# Sheet_X_link.net
KiCad netlist of a schematic drawn in Altium Designer
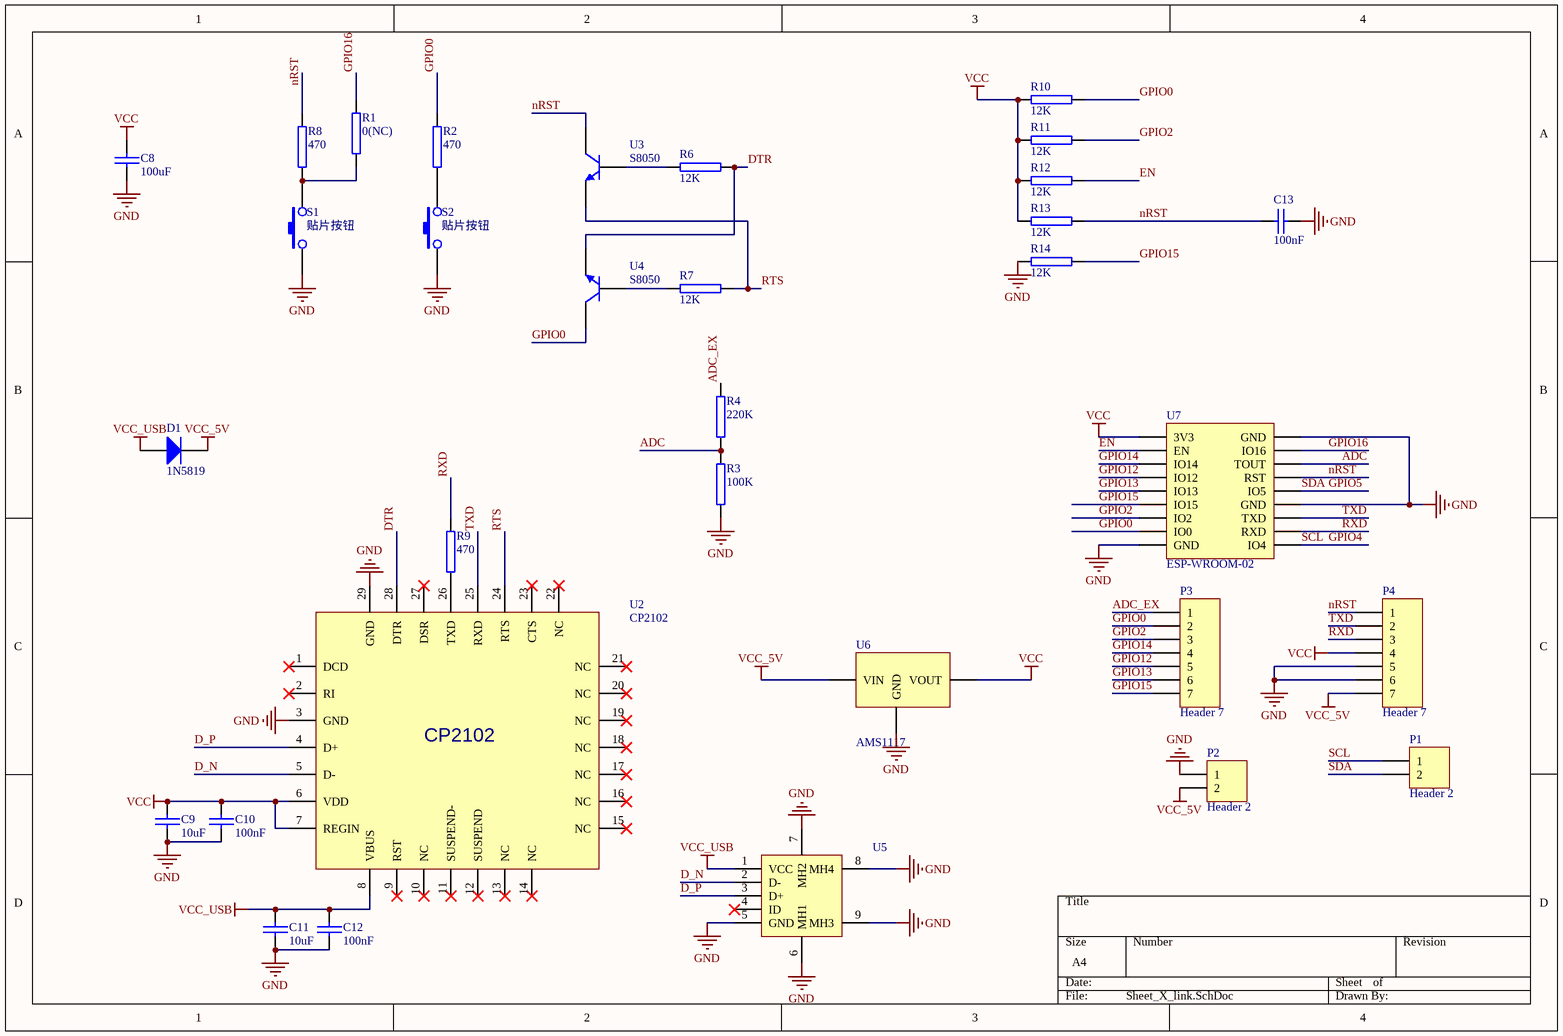
[diagram p0: Sheet_X_link.SchDoc]

(export (version "E")
  (design (tool "Eeschema 10.0.6"))
  (components
    (comp (ref "C8")
      (value "100uF")
      (footprint "C3528")
      (description "贴片电容")
      (libsource (lib "Schlib_OLEDMCU") (part "C0603"))
    )
    (comp (ref "C9")
      (value "10uF")
      (footprint "C0603")
      (description "贴片电容")
      (libsource (lib "Schlib_OLEDMCU") (part "C0603"))
    )
    (comp (ref "C10")
      (value "100nF")
      (footprint "C0603")
      (description "贴片电容")
      (libsource (lib "Schlib_OLEDMCU") (part "C0603"))
    )
    (comp (ref "C11")
      (value "10uF")
      (footprint "C0603")
      (description "贴片电容")
      (libsource (lib "Schlib_OLEDMCU") (part "C0603"))
    )
    (comp (ref "C12")
      (value "100nF")
      (footprint "C0603")
      (description "贴片电容")
      (libsource (lib "Schlib_OLEDMCU") (part "C0603"))
    )
    (comp (ref "C13")
      (value "100nF")
      (footprint "C0603")
      (description "贴片电容")
      (libsource (lib "Schlib_OLEDMCU") (part "C0603"))
    )
    (comp (ref "D1")
      (value "1N5819")
      (footprint "1n4148")
      (description "二极管")
      (libsource (lib "Schlib_OLEDMCU") (part "1N4148"))
    )
    (comp (ref "P1")
      (value "Header 2")
      (footprint "HDR1X2")
      (description "Header, 2-Pin")
      (fields (field (name "PUBLISHER") "Altium Limited"))
      (libsource (lib "Miscellaneous Connectors") (part "Header 2"))
    )
    (comp (ref "P2")
      (value "Header 2")
      (footprint "HDR1X2")
      (description "Header, 2-Pin")
      (fields (field (name "PUBLISHER") "Altium Limited"))
      (libsource (lib "Miscellaneous Connectors") (part "Header 2"))
    )
    (comp (ref "P3")
      (value "Header 7")
      (footprint "HDR1X7")
      (description "Header, 7-Pin")
      (fields (field (name "PUBLISHER") "Altium Limited"))
      (libsource (lib "Miscellaneous Connectors") (part "Header 7"))
    )
    (comp (ref "P4")
      (value "Header 7")
      (footprint "HDR1X7")
      (description "Header, 7-Pin")
      (fields (field (name "PUBLISHER") "Altium Limited"))
      (libsource (lib "Miscellaneous Connectors") (part "Header 7"))
    )
    (comp (ref "R1")
      (value "0(NC)")
      (footprint "R0603")
      (description "贴片电阻")
      (libsource (lib "Schlib_OLEDMCU") (part "R0603"))
    )
    (comp (ref "R2")
      (value "470")
      (footprint "R0603")
      (description "贴片电阻")
      (libsource (lib "Schlib_OLEDMCU") (part "R0603"))
    )
    (comp (ref "R3")
      (value "100K")
      (footprint "R0603")
      (description "贴片电阻")
      (libsource (lib "Schlib_OLEDMCU") (part "R0603"))
    )
    (comp (ref "R4")
      (value "220K")
      (footprint "R0603")
      (description "贴片电阻")
      (libsource (lib "Schlib_OLEDMCU") (part "R0603"))
    )
    (comp (ref "R6")
      (value "12K")
      (footprint "R0603")
      (description "贴片电阻")
      (libsource (lib "Schlib_OLEDMCU") (part "R0603"))
    )
    (comp (ref "R7")
      (value "12K")
      (footprint "R0603")
      (description "贴片电阻")
      (libsource (lib "Schlib_OLEDMCU") (part "R0603"))
    )
    (comp (ref "R8")
      (value "470")
      (footprint "R0603")
      (description "贴片电阻")
      (libsource (lib "Schlib_OLEDMCU") (part "R0603"))
    )
    (comp (ref "R9")
      (value "470")
      (footprint "R0603")
      (description "贴片电阻")
      (libsource (lib "Schlib_OLEDMCU") (part "R0603"))
    )
    (comp (ref "R10")
      (value "12K")
      (footprint "R0603")
      (description "贴片电阻")
      (libsource (lib "Schlib_OLEDMCU") (part "R0603"))
    )
    (comp (ref "R11")
      (value "12K")
      (footprint "R0603")
      (description "贴片电阻")
      (libsource (lib "Schlib_OLEDMCU") (part "R0603"))
    )
    (comp (ref "R12")
      (value "12K")
      (footprint "R0603")
      (description "贴片电阻")
      (libsource (lib "Schlib_OLEDMCU") (part "R0603"))
    )
    (comp (ref "R13")
      (value "12K")
      (footprint "R0603")
      (description "贴片电阻")
      (libsource (lib "Schlib_OLEDMCU") (part "R0603"))
    )
    (comp (ref "R14")
      (value "12K")
      (footprint "R0603")
      (description "贴片电阻")
      (libsource (lib "Schlib_OLEDMCU") (part "R0603"))
    )
    (comp (ref "S1")
      (value "贴片按钮")
      (footprint "switch")
      (description "3*4*2mm开关")
      (libsource (lib "Schlib_OLEDMCU") (part "Switch"))
    )
    (comp (ref "S2")
      (value "贴片按钮")
      (footprint "switch")
      (description "3*4*2mm开关")
      (libsource (lib "Schlib_OLEDMCU") (part "Switch"))
    )
    (comp (ref "U2")
      (value "CP2102")
      (footprint "cp2102")
      (description "USB转串口芯片")
      (libsource (lib "Schlib_OLEDMCU") (part "CP2102"))
    )
    (comp (ref "U3")
      (value "S8050")
      (footprint "s8050")
      (description "三极管")
      (libsource (lib "Schlib_OLEDMCU") (part "S8050"))
    )
    (comp (ref "U4")
      (value "S8050")
      (footprint "s8050")
      (description "三极管")
      (libsource (lib "Schlib_OLEDMCU") (part "S8050"))
    )
    (comp (ref "U5")
      (value "MicroUSB-5P")
      (footprint "MICROUSB_5S")
      (description "Micro USB插脚")
      (libsource (lib "Schlib_OLEDMCU") (part "MicroUSB_5S"))
    )
    (comp (ref "U6")
      (value "AMS1117")
      (footprint "AMS1117")
      (description "3.3V稳压芯片")
      (libsource (lib "Schlib_OLEDMCU") (part "AMS1117"))
    )
    (comp (ref "U7")
      (value "ESP-WROOM-02")
      (footprint "ESP-WROOM-02")
      (description "WiFi芯片")
      (libsource (lib "Schlib_OLEDMCU") (part "ESP-WROOM-02"))
    )
  )
  (nets
    (net (code "1") (name "/ADC") (class "Default")
      (node (ref "R3") (pin "2") (pinfunction "2_2") (pintype "passive"))
      (node (ref "R4") (pin "1") (pinfunction "1_1") (pintype "passive"))
      (node (ref "U7") (pin "15") (pinfunction "TOUT_15") (pintype "passive"))
    )
    (net (code "2") (name "/ADC_EX") (class "Default")
      (node (ref "P3") (pin "1") (pinfunction "1_1") (pintype "passive"))
      (node (ref "R4") (pin "2") (pinfunction "2_2") (pintype "passive"))
    )
    (net (code "3") (name "/DTR") (class "Default")
      (node (ref "R6") (pin "2") (pinfunction "2_2") (pintype "passive"))
      (node (ref "U2") (pin "28") (pinfunction "DTR_28") (pintype "passive"))
      (node (ref "U4") (pin "2") (pinfunction "E_2") (pintype "passive"))
    )
    (net (code "4") (name "/D_N") (class "Default")
      (node (ref "U2") (pin "5") (pinfunction "D-_5") (pintype "passive"))
      (node (ref "U5") (pin "2") (pinfunction "D-_2") (pintype "passive"))
    )
    (net (code "5") (name "/D_P") (class "Default")
      (node (ref "U2") (pin "4") (pinfunction "D+_4") (pintype "passive"))
      (node (ref "U5") (pin "3") (pinfunction "D+_3") (pintype "passive"))
    )
    (net (code "6") (name "/EN") (class "Default")
      (node (ref "R12") (pin "2") (pinfunction "2_2") (pintype "passive"))
      (node (ref "U7") (pin "1") (pinfunction "EN_1") (pintype "passive"))
    )
    (net (code "7") (name "/GPIO0") (class "Default")
      (node (ref "P3") (pin "2") (pinfunction "2_2") (pintype "passive"))
      (node (ref "R10") (pin "2") (pinfunction "2_2") (pintype "passive"))
      (node (ref "R2") (pin "2") (pinfunction "2_2") (pintype "passive"))
      (node (ref "U4") (pin "3") (pinfunction "C_3") (pintype "passive"))
      (node (ref "U7") (pin "7") (pinfunction "IO0_7") (pintype "passive"))
    )
    (net (code "8") (name "/GPIO2") (class "Default")
      (node (ref "P3") (pin "3") (pinfunction "3_3") (pintype "passive"))
      (node (ref "R11") (pin "2") (pinfunction "2_2") (pintype "passive"))
      (node (ref "U7") (pin "6") (pinfunction "IO2_6") (pintype "passive"))
    )
    (net (code "9") (name "/GPIO4") (class "Default")
      (node (ref "P1") (pin "1") (pinfunction "1_1") (pintype "passive"))
      (node (ref "U7") (pin "9") (pinfunction "IO4_9") (pintype "passive"))
    )
    (net (code "10") (name "/GPIO5") (class "Default")
      (node (ref "P1") (pin "2") (pinfunction "2_2") (pintype "passive"))
      (node (ref "U7") (pin "13") (pinfunction "IO5_13") (pintype "passive"))
    )
    (net (code "11") (name "/GPIO12") (class "Default")
      (node (ref "P3") (pin "5") (pinfunction "5_5") (pintype "passive"))
      (node (ref "U7") (pin "3") (pinfunction "IO12_3") (pintype "passive"))
    )
    (net (code "12") (name "/GPIO13") (class "Default")
      (node (ref "P3") (pin "6") (pinfunction "6_6") (pintype "passive"))
      (node (ref "U7") (pin "4") (pinfunction "IO13_4") (pintype "passive"))
    )
    (net (code "13") (name "/GPIO14") (class "Default")
      (node (ref "P3") (pin "4") (pinfunction "4_4") (pintype "passive"))
      (node (ref "U7") (pin "2") (pinfunction "IO14_2") (pintype "passive"))
    )
    (net (code "14") (name "/GPIO15") (class "Default")
      (node (ref "P3") (pin "7") (pinfunction "7_7") (pintype "passive"))
      (node (ref "R14") (pin "2") (pinfunction "2_2") (pintype "passive"))
      (node (ref "U7") (pin "5") (pinfunction "IO15_5") (pintype "passive"))
    )
    (net (code "15") (name "/GPIO16") (class "Default")
      (node (ref "R1") (pin "2") (pinfunction "2_2") (pintype "passive"))
      (node (ref "U7") (pin "16") (pinfunction "IO16_16") (pintype "passive"))
    )
    (net (code "16") (name "/RTS") (class "Default")
      (node (ref "R7") (pin "2") (pinfunction "2_2") (pintype "passive"))
      (node (ref "U2") (pin "24") (pinfunction "RTS_24") (pintype "passive"))
      (node (ref "U3") (pin "2") (pinfunction "E_2") (pintype "passive"))
    )
    (net (code "17") (name "/RXD") (class "Default")
      (node (ref "P4") (pin "3") (pinfunction "3_3") (pintype "passive"))
      (node (ref "R9") (pin "2") (pinfunction "2_2") (pintype "passive"))
      (node (ref "U7") (pin "10") (pinfunction "RXD_10") (pintype "passive"))
    )
    (net (code "18") (name "/TXD") (class "Default")
      (node (ref "P4") (pin "2") (pinfunction "2_2") (pintype "passive"))
      (node (ref "U2") (pin "25") (pinfunction "RXD_25") (pintype "passive"))
      (node (ref "U7") (pin "11") (pinfunction "TXD_11") (pintype "passive"))
    )
    (net (code "19") (name "/nRST") (class "Default")
      (node (ref "C13") (pin "1") (pinfunction "1_1") (pintype "passive"))
      (node (ref "P4") (pin "1") (pinfunction "1_1") (pintype "passive"))
      (node (ref "R13") (pin "2") (pinfunction "2_2") (pintype "passive"))
      (node (ref "R8") (pin "2") (pinfunction "2_2") (pintype "passive"))
      (node (ref "U3") (pin "3") (pinfunction "C_3") (pintype "passive"))
      (node (ref "U7") (pin "14") (pinfunction "RST_14") (pintype "passive"))
    )
    (net (code "20") (name "GND") (class "Default")
      (node (ref "C10") (pin "1") (pinfunction "1_1") (pintype "passive"))
      (node (ref "C11") (pin "1") (pinfunction "1_1") (pintype "passive"))
      (node (ref "C12") (pin "1") (pinfunction "1_1") (pintype "passive"))
      (node (ref "C13") (pin "2") (pinfunction "2_2") (pintype "passive"))
      (node (ref "C8") (pin "2") (pinfunction "2_2") (pintype "passive"))
      (node (ref "C9") (pin "1") (pinfunction "1_1") (pintype "passive"))
      (node (ref "P2") (pin "1") (pinfunction "1_1") (pintype "passive"))
      (node (ref "P4") (pin "5") (pinfunction "5_5") (pintype "passive"))
      (node (ref "P4") (pin "6") (pinfunction "6_6") (pintype "passive"))
      (node (ref "R14") (pin "1") (pinfunction "1_1") (pintype "passive"))
      (node (ref "R3") (pin "1") (pinfunction "1_1") (pintype "passive"))
      (node (ref "S1") (pin "1") (pinfunction "1_1") (pintype "passive"))
      (node (ref "S2") (pin "1") (pinfunction "1_1") (pintype "passive"))
      (node (ref "U2") (pin "29") (pinfunction "GND_29") (pintype "passive"))
      (node (ref "U2") (pin "3") (pinfunction "GND_3") (pintype "passive"))
      (node (ref "U5") (pin "5") (pinfunction "GND_5") (pintype "passive"))
      (node (ref "U5") (pin "6") (pinfunction "MH1_6") (pintype "passive"))
      (node (ref "U5") (pin "7") (pinfunction "MH2_7") (pintype "passive"))
      (node (ref "U5") (pin "8") (pinfunction "MH4_8") (pintype "passive"))
      (node (ref "U5") (pin "9") (pinfunction "MH3_9") (pintype "passive"))
      (node (ref "U6") (pin "1") (pinfunction "GND_1") (pintype "passive"))
      (node (ref "U7") (pin "12") (pinfunction "GND_12") (pintype "passive"))
      (node (ref "U7") (pin "17") (pinfunction "GND_17") (pintype "passive"))
      (node (ref "U7") (pin "8") (pinfunction "GND_8") (pintype "passive"))
    )
    (net (code "21") (name "Net-(R1-Pad1)") (class "Default")
      (node (ref "R1") (pin "1") (pinfunction "1_1") (pintype "passive"))
      (node (ref "R8") (pin "1") (pinfunction "1_1") (pintype "passive"))
      (node (ref "S1") (pin "2") (pinfunction "2_2") (pintype "passive"))
    )
    (net (code "22") (name "Net-(R2-Pad1)") (class "Default")
      (node (ref "R2") (pin "1") (pinfunction "1_1") (pintype "passive"))
      (node (ref "S2") (pin "2") (pinfunction "2_2") (pintype "passive"))
    )
    (net (code "23") (name "Net-(U2-TXD)") (class "Default")
      (node (ref "R9") (pin "1") (pinfunction "1_1") (pintype "passive"))
      (node (ref "U2") (pin "26") (pinfunction "TXD_26") (pintype "passive"))
    )
    (net (code "24") (name "Net-(U3-B)") (class "Default")
      (node (ref "R6") (pin "1") (pinfunction "1_1") (pintype "passive"))
      (node (ref "U3") (pin "1") (pinfunction "B_1") (pintype "passive"))
    )
    (net (code "25") (name "Net-(U4-B)") (class "Default")
      (node (ref "R7") (pin "1") (pinfunction "1_1") (pintype "passive"))
      (node (ref "U4") (pin "1") (pinfunction "B_1") (pintype "passive"))
    )
    (net (code "26") (name "VCC") (class "Default")
      (node (ref "C10") (pin "2") (pinfunction "2_2") (pintype "passive"))
      (node (ref "C8") (pin "1") (pinfunction "1_1") (pintype "passive"))
      (node (ref "C9") (pin "2") (pinfunction "2_2") (pintype "passive"))
      (node (ref "P4") (pin "4") (pinfunction "4_4") (pintype "passive"))
      (node (ref "R10") (pin "1") (pinfunction "1_1") (pintype "passive"))
      (node (ref "R11") (pin "1") (pinfunction "1_1") (pintype "passive"))
      (node (ref "R12") (pin "1") (pinfunction "1_1") (pintype "passive"))
      (node (ref "R13") (pin "1") (pinfunction "1_1") (pintype "passive"))
      (node (ref "U2") (pin "6") (pinfunction "VDD_6") (pintype "passive"))
      (node (ref "U2") (pin "7") (pinfunction "REGIN_7") (pintype "passive"))
      (node (ref "U6") (pin "2") (pinfunction "VOUT_2") (pintype "passive"))
      (node (ref "U7") (pin "0") (pinfunction "3V3_0") (pintype "passive"))
    )
    (net (code "27") (name "VCC_5V") (class "Default")
      (node (ref "D1") (pin "2") (pinfunction "K_2") (pintype "passive"))
      (node (ref "P2") (pin "2") (pinfunction "2_2") (pintype "passive"))
      (node (ref "P4") (pin "7") (pinfunction "7_7") (pintype "passive"))
      (node (ref "U6") (pin "3") (pinfunction "VIN_3") (pintype "passive"))
    )
    (net (code "28") (name "VCC_USB") (class "Default")
      (node (ref "C11") (pin "2") (pinfunction "2_2") (pintype "passive"))
      (node (ref "C12") (pin "2") (pinfunction "2_2") (pintype "passive"))
      (node (ref "D1") (pin "1") (pinfunction "A_1") (pintype "passive"))
      (node (ref "U2") (pin "8") (pinfunction "VBUS_8") (pintype "passive"))
      (node (ref "U5") (pin "1") (pinfunction "VCC_1") (pintype "passive"))
    )
    (net (code "29") (name "unconnected-(U2-CTS-Pad23)") (class "Default")
      (node (ref "U2") (pin "23") (pinfunction "CTS_23") (pintype "passive+no_connect"))
    )
    (net (code "30") (name "unconnected-(U2-DCD-Pad1)") (class "Default")
      (node (ref "U2") (pin "1") (pinfunction "DCD_1") (pintype "passive+no_connect"))
    )
    (net (code "31") (name "unconnected-(U2-DSR-Pad27)") (class "Default")
      (node (ref "U2") (pin "27") (pinfunction "DSR_27") (pintype "passive+no_connect"))
    )
    (net (code "32") (name "unconnected-(U2-NC-Pad10)") (class "Default")
      (node (ref "U2") (pin "10") (pinfunction "NC_10") (pintype "passive+no_connect"))
    )
    (net (code "33") (name "unconnected-(U2-NC-Pad13)") (class "Default")
      (node (ref "U2") (pin "13") (pinfunction "NC_13") (pintype "passive+no_connect"))
    )
    (net (code "34") (name "unconnected-(U2-NC-Pad14)") (class "Default")
      (node (ref "U2") (pin "14") (pinfunction "NC_14") (pintype "passive+no_connect"))
    )
    (net (code "35") (name "unconnected-(U2-NC-Pad15)") (class "Default")
      (node (ref "U2") (pin "15") (pinfunction "NC_15") (pintype "passive+no_connect"))
    )
    (net (code "36") (name "unconnected-(U2-NC-Pad16)") (class "Default")
      (node (ref "U2") (pin "16") (pinfunction "NC_16") (pintype "passive+no_connect"))
    )
    (net (code "37") (name "unconnected-(U2-NC-Pad17)") (class "Default")
      (node (ref "U2") (pin "17") (pinfunction "NC_17") (pintype "passive+no_connect"))
    )
    (net (code "38") (name "unconnected-(U2-NC-Pad18)") (class "Default")
      (node (ref "U2") (pin "18") (pinfunction "NC_18") (pintype "passive+no_connect"))
    )
    (net (code "39") (name "unconnected-(U2-NC-Pad19)") (class "Default")
      (node (ref "U2") (pin "19") (pinfunction "NC_19") (pintype "passive+no_connect"))
    )
    (net (code "40") (name "unconnected-(U2-NC-Pad20)") (class "Default")
      (node (ref "U2") (pin "20") (pinfunction "NC_20") (pintype "passive+no_connect"))
    )
    (net (code "41") (name "unconnected-(U2-NC-Pad21)") (class "Default")
      (node (ref "U2") (pin "21") (pinfunction "NC_21") (pintype "passive+no_connect"))
    )
    (net (code "42") (name "unconnected-(U2-NC-Pad22)") (class "Default")
      (node (ref "U2") (pin "22") (pinfunction "NC_22") (pintype "passive+no_connect"))
    )
    (net (code "43") (name "unconnected-(U2-RI-Pad2)") (class "Default")
      (node (ref "U2") (pin "2") (pinfunction "RI_2") (pintype "passive+no_connect"))
    )
    (net (code "44") (name "unconnected-(U2-RST-Pad9)") (class "Default")
      (node (ref "U2") (pin "9") (pinfunction "RST_9") (pintype "passive+no_connect"))
    )
    (net (code "45") (name "unconnected-(U2-SUSPEND--Pad11)") (class "Default")
      (node (ref "U2") (pin "11") (pinfunction "SUSPEND-_11") (pintype "passive+no_connect"))
    )
    (net (code "46") (name "unconnected-(U2-SUSPEND-Pad12)") (class "Default")
      (node (ref "U2") (pin "12") (pinfunction "SUSPEND_12") (pintype "passive+no_connect"))
    )
    (net (code "47") (name "unconnected-(U5-ID-Pad4)") (class "Default")
      (node (ref "U5") (pin "4") (pinfunction "ID_4") (pintype "passive+no_connect"))
    )
  )
)
